# CSM32RV20_QFN_3V5V_V1_1.net
KiCad netlist of a schematic drawn in Altium Designer
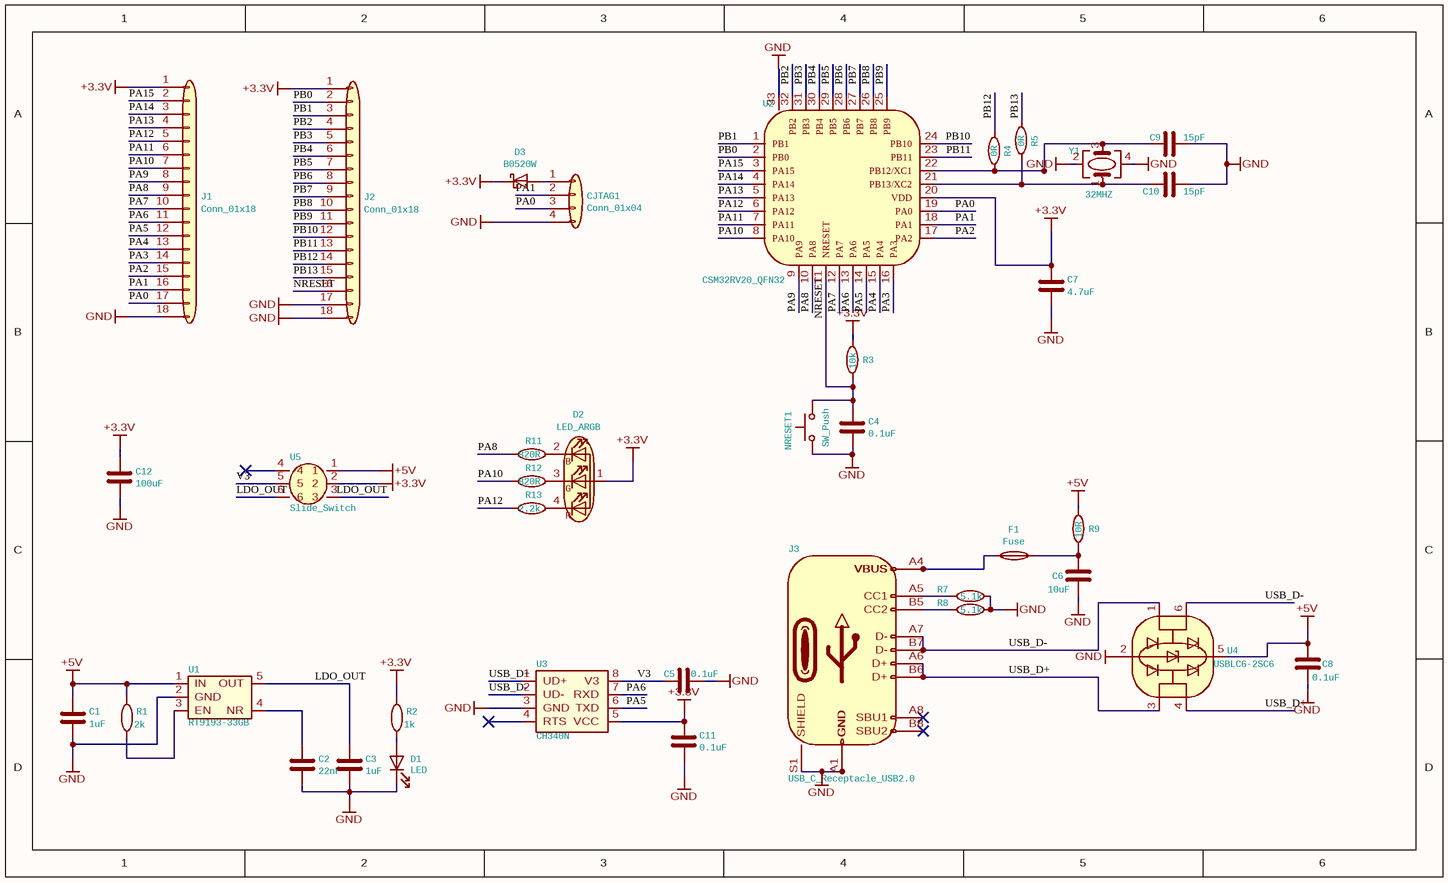
[diagram p0: CSM32RV20_QFN_3V5V_V1.1.SchDoc]

(export (version "E")
  (design (tool "Eeschema 10.0.6"))
  (components
    (comp (ref "C1") (value "1uF") (footprint "0402") (libsource (lib "altium-import") (part "root_0_1uF_")))
    (comp (ref "C2")
      (value "22nF")
      (footprint "0402")
      (libsource (lib "altium-import") (part "root_0_22nF_"))
    )
    (comp (ref "C3") (value "1uF") (footprint "0402") (libsource (lib "altium-import") (part "root_0_1uF_")))
    (comp (ref "C4") (value "0.1uF") (footprint "0402") (libsource (lib "") (part "root_0_0.1uF__2")))
    (comp (ref "C5") (value "0.1uF") (footprint "0402") (libsource (lib "") (part "root_0_0.1uF__4")))
    (comp (ref "C6")
      (value "10uF")
      (footprint "0402")
      (libsource (lib "altium-import") (part "root_0_10uF_"))
    )
    (comp (ref "C7")
      (value "4.7uF")
      (footprint "0402")
      (libsource (lib "altium-import") (part "root_0_0.1uF_"))
    )
    (comp (ref "C8") (value "0.1uF") (footprint "0402") (libsource (lib "") (part "root_0_0.1uF__3")))
    (comp (ref "C9")
      (value "15pF")
      (footprint "0402")
      (libsource (lib "altium-import") (part "root_0_15pF_"))
    )
    (comp (ref "C10")
      (value "15pF")
      (footprint "0402")
      (libsource (lib "altium-import") (part "root_0_15pF_"))
    )
    (comp (ref "C11") (value "0.1uF") (footprint "0402") (libsource (lib "") (part "root_0_0.1uF__1")))
    (comp (ref "C12")
      (value "100uF")
      (footprint "C1210")
      (libsource (lib "altium-import") (part "root_0_100uF_"))
    )
    (comp (ref "CJTAG1")
      (value "Conn_01x04")
      (footprint "PINHEADER_1X04_P2.54MM_VERTICAL")
      (libsource (lib "altium-import") (part "root_0_Conn_01x04_"))
    )
    (comp (ref "D1")
      (value "LED")
      (footprint "LED 0402")
      (libsource (lib "CSM32RV20_QFN_3V5V_V1.1") (part "LED"))
    )
    (comp (ref "D2")
      (value "LED_ARGB")
      (footprint "LED_RGB_1210")
      (libsource (lib "altium-import") (part "root_0_LED_ARGB_"))
    )
    (comp (ref "D3")
      (value "B0520W")
      (footprint "D_SOD-123")
      (libsource (lib "altium-import") (part "root_0_B0520W_"))
    )
    (comp (ref "F1")
      (value "Fuse")
      (footprint "FUSE_0805_2012METRIC")
      (libsource (lib "altium-import") (part "root_0_Fuse_"))
    )
    (comp (ref "J1")
      (value "Conn_01x18")
      (footprint "PINHEADER_1X18_P2.54MM_VERTICAL")
      (libsource (lib "altium-import") (part "root_0_Conn_01x18_"))
    )
    (comp (ref "J2")
      (value "Conn_01x18")
      (footprint "PINHEADER_1X18_P2.54MM_VERTICAL")
      (libsource (lib "") (part "root_0_Conn_01x18__1"))
    )
    (comp (ref "J3")
      (value "USB_C_Receptacle_USB2.0")
      (footprint "USB-C-SMD_KH-TYPE-C-16P")
      (libsource (lib "CSM32RV20_QFN_3V5V_V1.1") (part "USB_C_Receptacle_USB2.0"))
    )
    (comp (ref "NRESET1")
      (value "SW_Push")
      (footprint "SW_PUSH_SPST_NO_ALPS_SKRK")
      (libsource (lib "altium-import") (part "root_0_SW_Push_"))
    )
    (comp (ref "R1") (value "2k") (footprint "0402") (libsource (lib "altium-import") (part "root_0_2k_")))
    (comp (ref "R2") (value "1k") (footprint "0402") (libsource (lib "altium-import") (part "root_0_1k_")))
    (comp (ref "R3") (value "10k") (footprint "0402") (libsource (lib "altium-import") (part "root_0_10k_")))
    (comp (ref "R4") (value "0R") (footprint "0402") (libsource (lib "") (part "root_0_0R__1")))
    (comp (ref "R5") (value "0R") (footprint "0402") (libsource (lib "altium-import") (part "root_0_0R_")))
    (comp (ref "R7")
      (value "5.1k")
      (footprint "0402")
      (libsource (lib "altium-import") (part "root_0_5.1k_"))
    )
    (comp (ref "R8")
      (value "5.1k")
      (footprint "0402")
      (libsource (lib "altium-import") (part "root_0_5.1k_"))
    )
    (comp (ref "R9") (value "10R") (footprint "0402") (libsource (lib "altium-import") (part "root_0_10R_")))
    (comp (ref "R11")
      (value "820R")
      (footprint "0402")
      (libsource (lib "altium-import") (part "root_0_820R_"))
    )
    (comp (ref "R12")
      (value "820R")
      (footprint "0402")
      (libsource (lib "altium-import") (part "root_0_820R_"))
    )
    (comp (ref "R13")
      (value "2.2k")
      (footprint "0402")
      (libsource (lib "altium-import") (part "root_0_2.2k_"))
    )
    (comp (ref "U1")
      (value "RT9193-33GB")
      (footprint "SOT-23-5")
      (libsource (lib "CSM32RV20_QFN_3V5V_V1.0") (part "RT9193-33GB"))
    )
    (comp (ref "U2")
      (value "CSM32RV20_QFN32")
      (footprint "QFN-32-1EP_4X4MM_P0.4MM_EP2.65X2.65MM_THERMALVIAS")
      (libsource (lib "CSM32RV20_QFN_3V5V_V1.1") (part "CSM32RV20_QFN32"))
    )
    (comp (ref "U3")
      (value "CH340N")
      (footprint "SOP-8-1EP_6X5MM_P1.27MM")
      (libsource (lib "CSM32RV20_QFN_3V5V_V1.0") (part "CH340N"))
    )
    (comp (ref "U4")
      (value "USBLC6-2SC6")
      (footprint "SOT-23-6")
      (libsource (lib "altium-import") (part "root_0_USBLC6-2SC6_"))
    )
    (comp (ref "U5")
      (value "Slide_Switch")
      (footprint "SLIDE_SWITCH_SMD")
      (libsource (lib "CSM32RV20_QFN_3V5V_V1.0") (part "Slide_Switch"))
    )
    (comp (ref "Y1")
      (value "32MHZ")
      (footprint "CRYSTAL_SMD_ABRACON_ABM8G-4PIN_3.2X2.5MM")
      (libsource (lib "altium-import") (part "root_0_32MHZ_"))
    )
  )
  (nets
    (net (code "1") (name "+3.3V") (class "Default")
      (node (ref "C11") (pin "1") (pintype "passive"))
      (node (ref "C12") (pin "1") (pintype "passive"))
      (node (ref "C7") (pin "1") (pintype "passive"))
      (node (ref "D2") (pin "1") (pinfunction "A_1") (pintype "passive"))
      (node (ref "D3") (pin "1") (pinfunction "K_1") (pintype "passive"))
      (node (ref "J1") (pin "1") (pinfunction "Pin_1_1") (pintype "passive"))
      (node (ref "J2") (pin "1") (pinfunction "Pin_1_1") (pintype "passive"))
      (node (ref "R2") (pin "1") (pintype "passive"))
      (node (ref "R3") (pin "1") (pintype "passive"))
      (node (ref "U2") (pin "20") (pinfunction "VDD_20") (pintype "passive"))
      (node (ref "U3") (pin "5") (pinfunction "VCC_5") (pintype "passive"))
      (node (ref "U5") (pin "2") (pinfunction "2_2") (pintype "passive"))
    )
    (net (code "2") (name "+5V") (class "Default")
      (node (ref "C1") (pin "1") (pintype "passive"))
      (node (ref "C8") (pin "2") (pintype "passive"))
      (node (ref "R1") (pin "1") (pintype "passive"))
      (node (ref "R9") (pin "1") (pintype "passive"))
      (node (ref "U1") (pin "1") (pinfunction "IN_1") (pintype "passive"))
      (node (ref "U4") (pin "5") (pinfunction "VBUS_5") (pintype "passive"))
      (node (ref "U5") (pin "1") (pinfunction "1_1") (pintype "passive"))
    )
    (net (code "3") (name "/LDO_OUT") (class "Default")
      (node (ref "C3") (pin "1") (pintype "passive"))
      (node (ref "U1") (pin "5") (pinfunction "OUT_5") (pintype "passive"))
      (node (ref "U5") (pin "3") (pinfunction "3_3") (pintype "passive"))
      (node (ref "U5") (pin "6") (pinfunction "6_6") (pintype "passive"))
    )
    (net (code "4") (name "/NRESET") (class "Default")
      (node (ref "C4") (pin "1") (pintype "passive"))
      (node (ref "J2") (pin "16") (pinfunction "Pin_16_16") (pintype "passive"))
      (node (ref "NRESET1") (pin "2") (pinfunction "2_2") (pintype "passive"))
      (node (ref "R3") (pin "2") (pintype "passive"))
      (node (ref "U2") (pin "11") (pinfunction "NRESET_11") (pintype "passive"))
    )
    (net (code "5") (name "/PA0") (class "Default")
      (node (ref "CJTAG1") (pin "3") (pinfunction "Pin_3_3") (pintype "passive"))
      (node (ref "J1") (pin "17") (pinfunction "Pin_17_17") (pintype "passive"))
      (node (ref "U2") (pin "19") (pinfunction "PA0_19") (pintype "passive"))
    )
    (net (code "6") (name "/PA1") (class "Default")
      (node (ref "CJTAG1") (pin "2") (pinfunction "Pin_2_2") (pintype "passive"))
      (node (ref "J1") (pin "16") (pinfunction "Pin_16_16") (pintype "passive"))
      (node (ref "U2") (pin "18") (pinfunction "PA1_18") (pintype "passive"))
    )
    (net (code "7") (name "/PA2") (class "Default")
      (node (ref "J1") (pin "15") (pinfunction "Pin_15_15") (pintype "passive"))
      (node (ref "U2") (pin "17") (pinfunction "PA2_17") (pintype "passive"))
    )
    (net (code "8") (name "/PA3") (class "Default")
      (node (ref "J1") (pin "14") (pinfunction "Pin_14_14") (pintype "passive"))
      (node (ref "U2") (pin "16") (pinfunction "PA3_16") (pintype "passive"))
    )
    (net (code "9") (name "/PA4") (class "Default")
      (node (ref "J1") (pin "13") (pinfunction "Pin_13_13") (pintype "passive"))
      (node (ref "U2") (pin "15") (pinfunction "PA4_15") (pintype "passive"))
    )
    (net (code "10") (name "/PA5") (class "Default")
      (node (ref "J1") (pin "12") (pinfunction "Pin_12_12") (pintype "passive"))
      (node (ref "U2") (pin "14") (pinfunction "PA5_14") (pintype "passive"))
      (node (ref "U3") (pin "6") (pinfunction "TXD_6") (pintype "passive"))
    )
    (net (code "11") (name "/PA6") (class "Default")
      (node (ref "J1") (pin "11") (pinfunction "Pin_11_11") (pintype "passive"))
      (node (ref "U2") (pin "13") (pinfunction "PA6_13") (pintype "passive"))
      (node (ref "U3") (pin "7") (pinfunction "RXD_7") (pintype "passive"))
    )
    (net (code "12") (name "/PA7") (class "Default")
      (node (ref "J1") (pin "10") (pinfunction "Pin_10_10") (pintype "passive"))
      (node (ref "U2") (pin "12") (pinfunction "PA7_12") (pintype "passive"))
    )
    (net (code "13") (name "/PA8") (class "Default")
      (node (ref "J1") (pin "9") (pinfunction "Pin_9_9") (pintype "passive"))
      (node (ref "R11") (pin "2") (pintype "passive"))
      (node (ref "U2") (pin "10") (pinfunction "PA8_10") (pintype "passive"))
    )
    (net (code "14") (name "/PA9") (class "Default")
      (node (ref "J1") (pin "8") (pinfunction "Pin_8_8") (pintype "passive"))
      (node (ref "U2") (pin "9") (pinfunction "PA9_9") (pintype "passive"))
    )
    (net (code "15") (name "/PA10") (class "Default")
      (node (ref "J1") (pin "7") (pinfunction "Pin_7_7") (pintype "passive"))
      (node (ref "R12") (pin "2") (pintype "passive"))
      (node (ref "U2") (pin "8") (pinfunction "PA10_8") (pintype "passive"))
    )
    (net (code "16") (name "/PA11") (class "Default")
      (node (ref "J1") (pin "6") (pinfunction "Pin_6_6") (pintype "passive"))
      (node (ref "U2") (pin "7") (pinfunction "PA11_7") (pintype "passive"))
    )
    (net (code "17") (name "/PA12") (class "Default")
      (node (ref "J1") (pin "5") (pinfunction "Pin_5_5") (pintype "passive"))
      (node (ref "R13") (pin "2") (pintype "passive"))
      (node (ref "U2") (pin "6") (pinfunction "PA12_6") (pintype "passive"))
    )
    (net (code "18") (name "/PA13") (class "Default")
      (node (ref "J1") (pin "4") (pinfunction "Pin_4_4") (pintype "passive"))
      (node (ref "U2") (pin "5") (pinfunction "PA13_5") (pintype "passive"))
    )
    (net (code "19") (name "/PA14") (class "Default")
      (node (ref "J1") (pin "3") (pinfunction "Pin_3_3") (pintype "passive"))
      (node (ref "U2") (pin "4") (pinfunction "PA14_4") (pintype "passive"))
    )
    (net (code "20") (name "/PA15") (class "Default")
      (node (ref "J1") (pin "2") (pinfunction "Pin_2_2") (pintype "passive"))
      (node (ref "U2") (pin "3") (pinfunction "PA15_3") (pintype "passive"))
    )
    (net (code "21") (name "/PB0") (class "Default")
      (node (ref "J2") (pin "2") (pinfunction "Pin_2_2") (pintype "passive"))
      (node (ref "U2") (pin "2") (pinfunction "PB0_2") (pintype "passive"))
    )
    (net (code "22") (name "/PB1") (class "Default")
      (node (ref "J2") (pin "3") (pinfunction "Pin_3_3") (pintype "passive"))
      (node (ref "U2") (pin "1") (pinfunction "PB1_1") (pintype "passive"))
    )
    (net (code "23") (name "/PB2") (class "Default")
      (node (ref "J2") (pin "4") (pinfunction "Pin_4_4") (pintype "passive"))
      (node (ref "U2") (pin "32") (pinfunction "PB2_32") (pintype "passive"))
    )
    (net (code "24") (name "/PB3") (class "Default")
      (node (ref "J2") (pin "5") (pinfunction "Pin_5_5") (pintype "passive"))
      (node (ref "U2") (pin "31") (pinfunction "PB3_31") (pintype "passive"))
    )
    (net (code "25") (name "/PB4") (class "Default")
      (node (ref "J2") (pin "6") (pinfunction "Pin_6_6") (pintype "passive"))
      (node (ref "U2") (pin "30") (pinfunction "PB4_30") (pintype "passive"))
    )
    (net (code "26") (name "/PB5") (class "Default")
      (node (ref "J2") (pin "7") (pinfunction "Pin_7_7") (pintype "passive"))
      (node (ref "U2") (pin "29") (pinfunction "PB5_29") (pintype "passive"))
    )
    (net (code "27") (name "/PB6") (class "Default")
      (node (ref "J2") (pin "8") (pinfunction "Pin_8_8") (pintype "passive"))
      (node (ref "U2") (pin "28") (pinfunction "PB6_28") (pintype "passive"))
    )
    (net (code "28") (name "/PB7") (class "Default")
      (node (ref "J2") (pin "9") (pinfunction "Pin_9_9") (pintype "passive"))
      (node (ref "U2") (pin "27") (pinfunction "PB7_27") (pintype "passive"))
    )
    (net (code "29") (name "/PB8") (class "Default")
      (node (ref "J2") (pin "10") (pinfunction "Pin_10_10") (pintype "passive"))
      (node (ref "U2") (pin "26") (pinfunction "PB8_26") (pintype "passive"))
    )
    (net (code "30") (name "/PB9") (class "Default")
      (node (ref "J2") (pin "11") (pinfunction "Pin_11_11") (pintype "passive"))
      (node (ref "U2") (pin "25") (pinfunction "PB9_25") (pintype "passive"))
    )
    (net (code "31") (name "/PB10") (class "Default")
      (node (ref "J2") (pin "12") (pinfunction "Pin_12_12") (pintype "passive"))
      (node (ref "U2") (pin "24") (pinfunction "PB10_24") (pintype "passive"))
    )
    (net (code "32") (name "/PB11") (class "Default")
      (node (ref "J2") (pin "13") (pinfunction "Pin_13_13") (pintype "passive"))
      (node (ref "U2") (pin "23") (pinfunction "PB11_23") (pintype "passive"))
    )
    (net (code "33") (name "/PB12") (class "Default")
      (node (ref "J2") (pin "14") (pinfunction "Pin_14_14") (pintype "passive"))
      (node (ref "R4") (pin "1") (pintype "passive"))
    )
    (net (code "34") (name "/PB13") (class "Default")
      (node (ref "J2") (pin "15") (pinfunction "Pin_15_15") (pintype "passive"))
      (node (ref "R5") (pin "1") (pintype "passive"))
    )
    (net (code "35") (name "/USB_D+") (class "Default")
      (node (ref "J3") (pin "A6") (pinfunction "D+_A6") (pintype "passive"))
      (node (ref "J3") (pin "B6") (pinfunction "D+_B6") (pintype "passive"))
      (node (ref "U3") (pin "1") (pinfunction "UD+_1") (pintype "passive"))
      (node (ref "U4") (pin "3") (pinfunction "I/O2_3") (pintype "passive"))
      (node (ref "U4") (pin "4") (pinfunction "I/O2_4") (pintype "passive"))
    )
    (net (code "36") (name "/USB_D-") (class "Default")
      (node (ref "J3") (pin "A7") (pinfunction "D-_A7") (pintype "passive"))
      (node (ref "J3") (pin "B7") (pinfunction "D-_B7") (pintype "passive"))
      (node (ref "U3") (pin "2") (pinfunction "UD-_2") (pintype "passive"))
      (node (ref "U4") (pin "1") (pinfunction "I/O1_1") (pintype "passive"))
      (node (ref "U4") (pin "6") (pinfunction "I/O1_6") (pintype "passive"))
    )
    (net (code "37") (name "/V3") (class "Default")
      (node (ref "C5") (pin "2") (pintype "passive"))
      (node (ref "U3") (pin "8") (pinfunction "V3_8") (pintype "passive"))
      (node (ref "U5") (pin "5") (pinfunction "5_5") (pintype "passive"))
    )
    (net (code "38") (name "GND") (class "Default")
      (node (ref "C1") (pin "2") (pintype "passive"))
      (node (ref "C10") (pin "1") (pintype "passive"))
      (node (ref "C11") (pin "2") (pintype "passive"))
      (node (ref "C12") (pin "2") (pintype "passive"))
      (node (ref "C2") (pin "2") (pintype "passive"))
      (node (ref "C3") (pin "2") (pintype "passive"))
      (node (ref "C4") (pin "2") (pintype "passive"))
      (node (ref "C5") (pin "1") (pintype "passive"))
      (node (ref "C6") (pin "1") (pintype "passive"))
      (node (ref "C7") (pin "2") (pintype "passive"))
      (node (ref "C8") (pin "1") (pintype "passive"))
      (node (ref "C9") (pin "1") (pintype "passive"))
      (node (ref "CJTAG1") (pin "4") (pinfunction "Pin_4_4") (pintype "passive"))
      (node (ref "D1") (pin "2") (pinfunction "K_2") (pintype "passive"))
      (node (ref "J1") (pin "18") (pinfunction "Pin_18_18") (pintype "passive"))
      (node (ref "J2") (pin "17") (pinfunction "Pin_17_17") (pintype "passive"))
      (node (ref "J2") (pin "18") (pinfunction "Pin_18_18") (pintype "passive"))
      (node (ref "J3") (pin "A1") (pinfunction "GND_A1") (pintype "passive"))
      (node (ref "J3") (pin "A12") (pinfunction "GND_A12") (pintype "passive"))
      (node (ref "J3") (pin "B1") (pinfunction "GND_B1") (pintype "passive"))
      (node (ref "J3") (pin "B12") (pinfunction "GND_B12") (pintype "passive"))
      (node (ref "J3") (pin "S1") (pinfunction "SHIELD_S1") (pintype "passive"))
      (node (ref "NRESET1") (pin "1") (pinfunction "1_1") (pintype "passive"))
      (node (ref "R7") (pin "2") (pintype "passive"))
      (node (ref "R8") (pin "2") (pintype "passive"))
      (node (ref "U1") (pin "2") (pinfunction "GND_2") (pintype "passive"))
      (node (ref "U2") (pin "33") (pinfunction "GND_33") (pintype "passive"))
      (node (ref "U3") (pin "3") (pinfunction "GND_3") (pintype "passive"))
      (node (ref "U4") (pin "2") (pinfunction "GND_2") (pintype "passive"))
      (node (ref "Y1") (pin "2") (pinfunction "2_2") (pintype "passive"))
      (node (ref "Y1") (pin "4") (pinfunction "4_4") (pintype "passive"))
    )
    (net (code "39") (name "Net-(C6-Pad2)") (class "Default")
      (node (ref "C6") (pin "2") (pintype "passive"))
      (node (ref "F1") (pin "1") (pintype "passive"))
      (node (ref "R9") (pin "2") (pintype "passive"))
    )
    (net (code "40") (name "Net-(CJTAG1-Pin_1)") (class "Default")
      (node (ref "CJTAG1") (pin "1") (pinfunction "Pin_1_1") (pintype "passive"))
      (node (ref "D3") (pin "2") (pinfunction "A_2") (pintype "passive"))
    )
    (net (code "41") (name "Net-(D1-A)") (class "Default")
      (node (ref "D1") (pin "1") (pinfunction "A_1") (pintype "passive"))
      (node (ref "R2") (pin "2") (pintype "passive"))
    )
    (net (code "42") (name "Net-(D2-BK)") (class "Default")
      (node (ref "D2") (pin "4") (pinfunction "BK_4") (pintype "passive"))
      (node (ref "R13") (pin "1") (pintype "passive"))
    )
    (net (code "43") (name "Net-(D2-GK)") (class "Default")
      (node (ref "D2") (pin "3") (pinfunction "GK_3") (pintype "passive"))
      (node (ref "R12") (pin "1") (pintype "passive"))
    )
    (net (code "44") (name "Net-(D2-RK)") (class "Default")
      (node (ref "D2") (pin "2") (pinfunction "RK_2") (pintype "passive"))
      (node (ref "R11") (pin "1") (pintype "passive"))
    )
    (net (code "45") (name "Net-(F1-Pad2)") (class "Default")
      (node (ref "F1") (pin "2") (pintype "passive"))
      (node (ref "J3") (pin "A4") (pinfunction "VBUS_A4") (pintype "passive"))
      (node (ref "J3") (pin "A9") (pinfunction "VBUS_A9") (pintype "passive"))
      (node (ref "J3") (pin "B4") (pinfunction "VBUS_B4") (pintype "passive"))
      (node (ref "J3") (pin "B9") (pinfunction "VBUS_B9") (pintype "passive"))
    )
    (net (code "46") (name "Net-(J3-CC1)") (class "Default")
      (node (ref "J3") (pin "A5") (pinfunction "CC1_A5") (pintype "passive"))
      (node (ref "R7") (pin "1") (pintype "passive"))
    )
    (net (code "47") (name "Net-(J3-CC2)") (class "Default")
      (node (ref "J3") (pin "B5") (pinfunction "CC2_B5") (pintype "passive"))
      (node (ref "R8") (pin "1") (pintype "passive"))
    )
    (net (code "48") (name "Net-(U1-EN)") (class "Default")
      (node (ref "R1") (pin "2") (pintype "passive"))
      (node (ref "U1") (pin "3") (pinfunction "EN_3") (pintype "passive"))
    )
    (net (code "49") (name "Net-(U1-NR)") (class "Default")
      (node (ref "C2") (pin "1") (pintype "passive"))
      (node (ref "U1") (pin "4") (pinfunction "NR_4") (pintype "passive"))
    )
    (net (code "50") (name "Net-(U2-PB12{slash}XC1)") (class "Default")
      (node (ref "C9") (pin "2") (pintype "passive"))
      (node (ref "R4") (pin "2") (pintype "passive"))
      (node (ref "U2") (pin "22") (pinfunction "PB12/XC1_22") (pintype "passive"))
      (node (ref "Y1") (pin "3") (pinfunction "3_3") (pintype "passive"))
    )
    (net (code "51") (name "Net-(U2-PB13{slash}XC2)") (class "Default")
      (node (ref "C10") (pin "2") (pintype "passive"))
      (node (ref "R5") (pin "2") (pintype "passive"))
      (node (ref "U2") (pin "21") (pinfunction "PB13/XC2_21") (pintype "passive"))
      (node (ref "Y1") (pin "1") (pinfunction "1_1") (pintype "passive"))
    )
    (net (code "52") (name "unconnected-(J3-SBU1-PadA8)") (class "Default")
      (node (ref "J3") (pin "A8") (pinfunction "SBU1_A8") (pintype "passive+no_connect"))
    )
    (net (code "53") (name "unconnected-(J3-SBU2-PadB8)") (class "Default")
      (node (ref "J3") (pin "B8") (pinfunction "SBU2_B8") (pintype "passive+no_connect"))
    )
    (net (code "54") (name "unconnected-(U3-RTS-Pad4)") (class "Default")
      (node (ref "U3") (pin "4") (pinfunction "RTS_4") (pintype "passive+no_connect"))
    )
    (net (code "55") (name "unconnected-(U5-Pad4)") (class "Default")
      (node (ref "U5") (pin "4") (pinfunction "4_4") (pintype "passive+no_connect"))
    )
  )
)
